# PWR_Supply-5_5V.net
KiCad netlist of a schematic drawn in Altium Designer
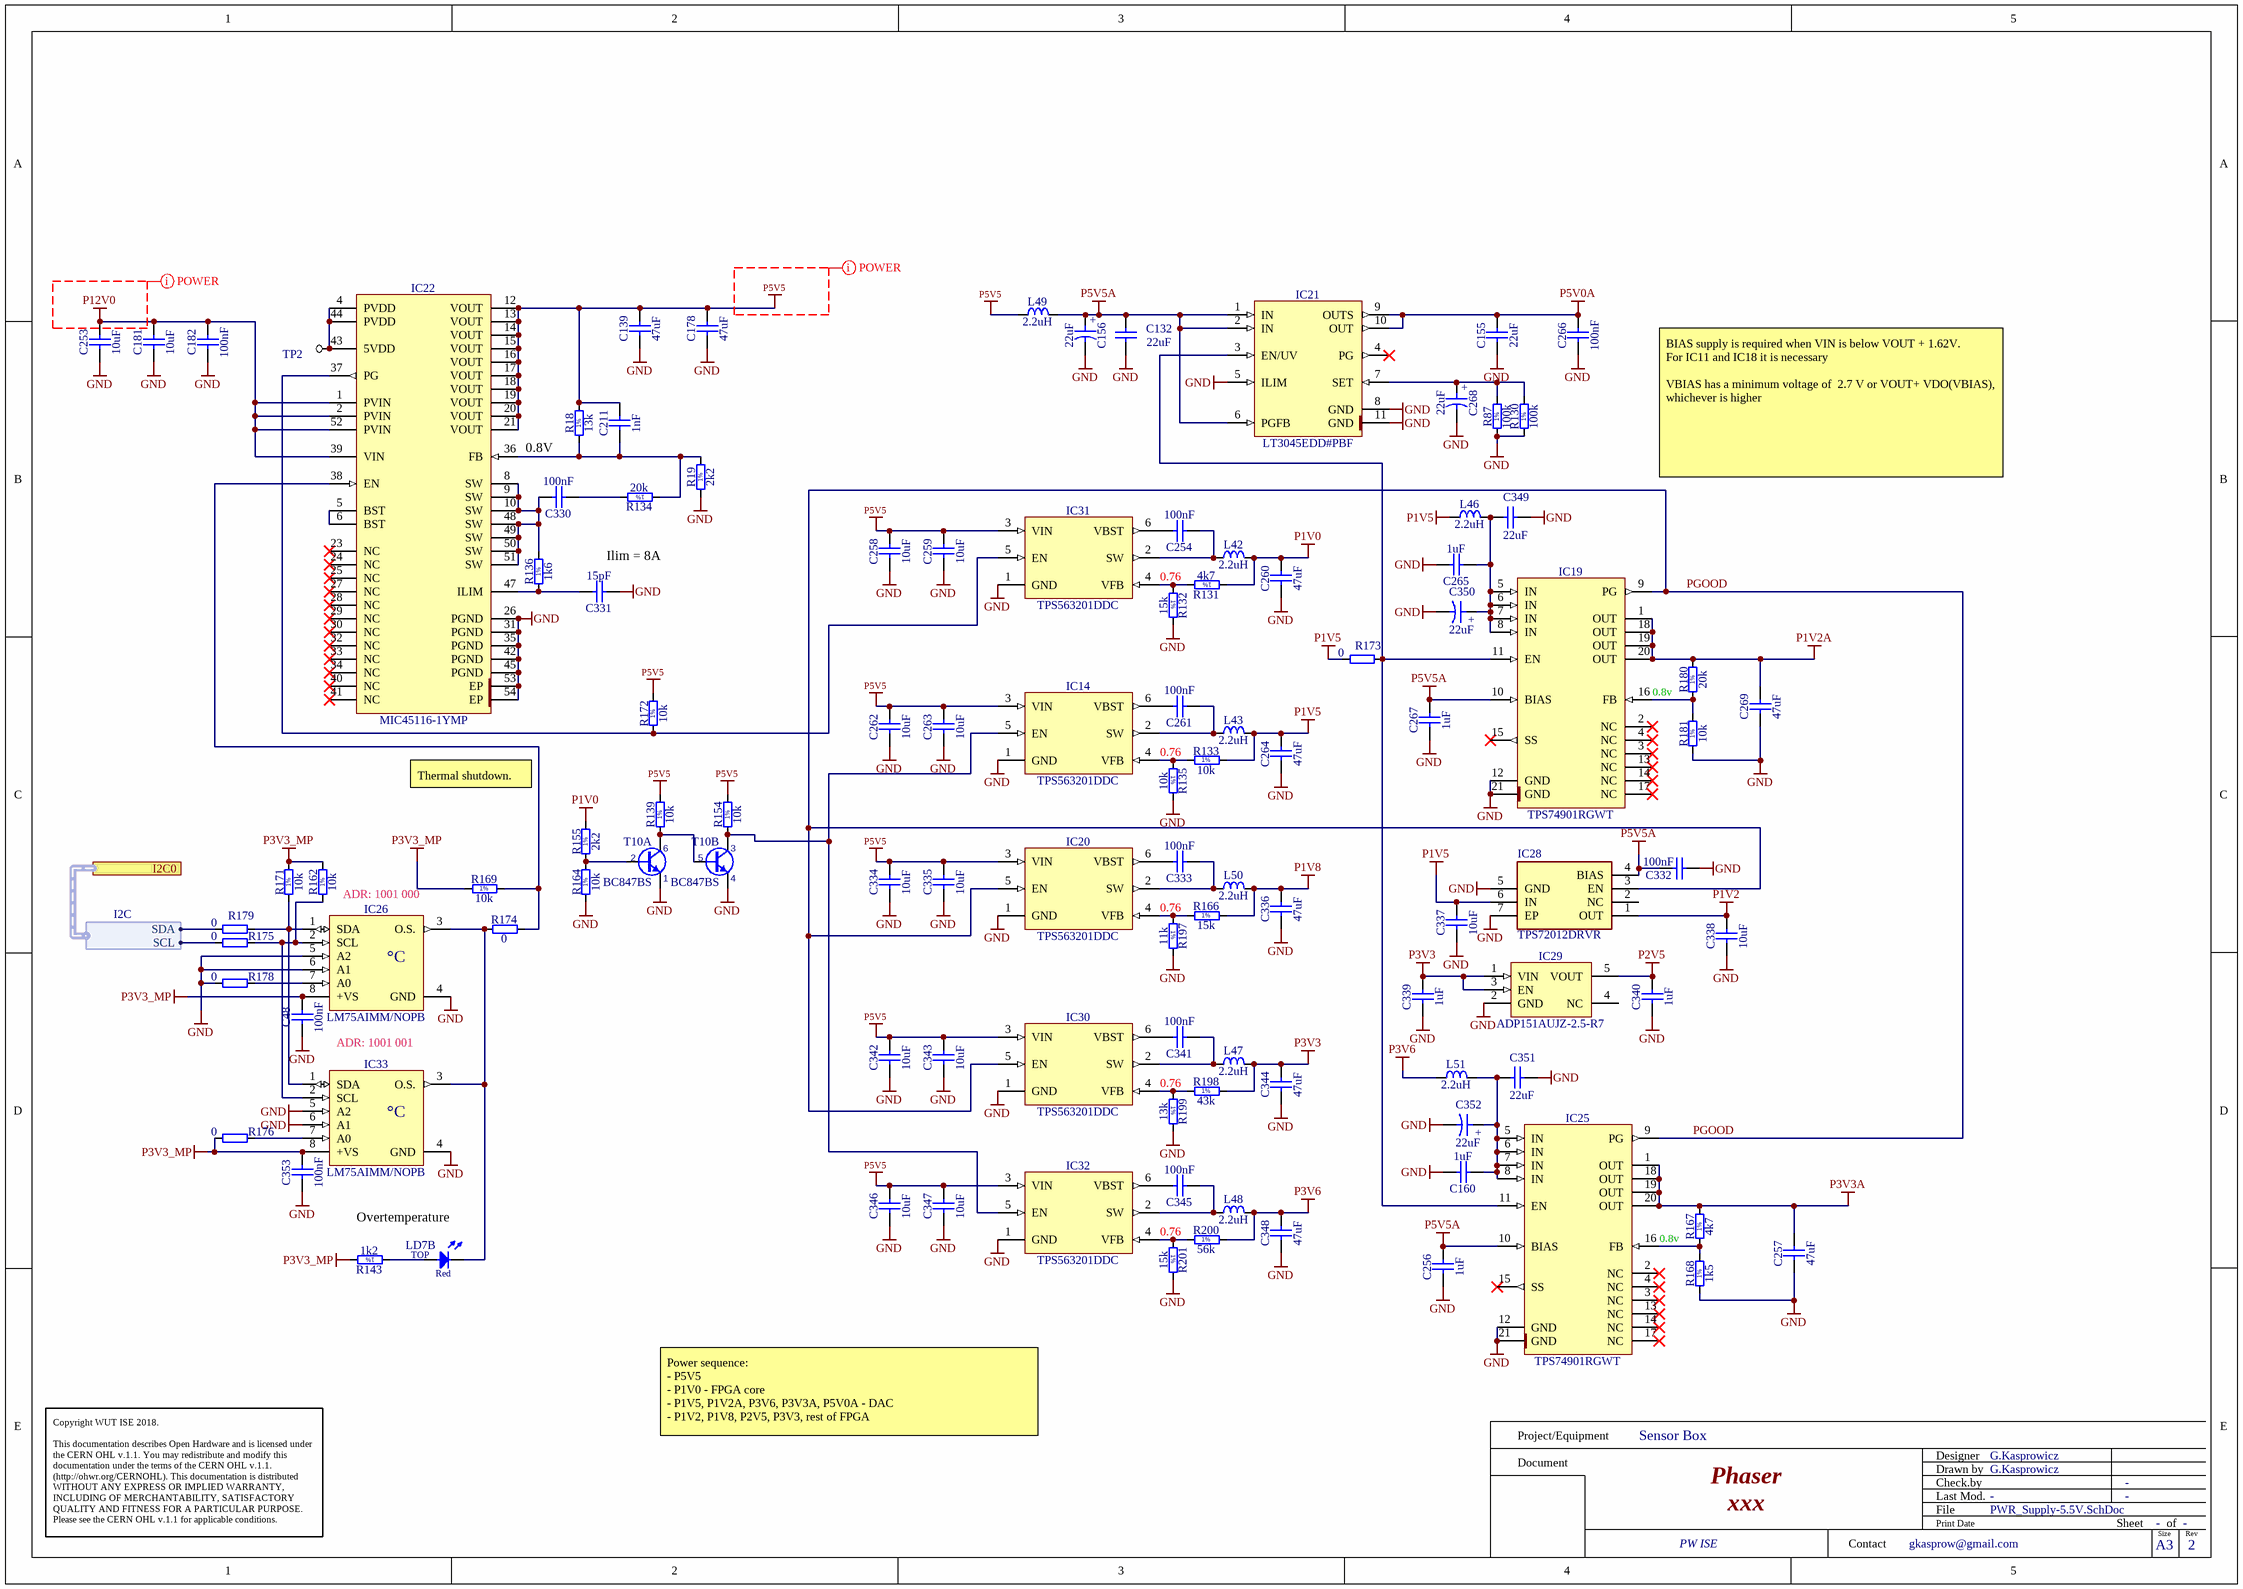
[diagram p0: PWR_Supply-5.5V.SchDoc]

(export (version "E")
  (design (tool "Eeschema 10.0.6"))
  (components
    (comp (ref "C48")
      (value "100nF")
      (footprint "CAPC1005X55N")
      (description "Non-polarised capacitor")
      (fields
        (field (name "PART NUMBER") "CC0402_100NF_16V_10%_X5R")
        (field (name "VOLTAGE") "16V")
        (field (name "AUTHOR") "CERN DEM JLC")
      )
      (libsource (lib "Capacitors") (part "Capacitor - non polarized"))
    )
    (comp (ref "C132")
      (value "22uF")
      (footprint "CAPC2012X135N")
      (description "Non-polarised capacitor")
      (fields
        (field (name "PART NUMBER") "CC0805_22UF_16V_10%_X5R")
        (field (name "VOLTAGE") "16V")
        (field (name "AUTHOR") "CERN DEM JLC")
      )
      (libsource (lib "Capacitors") (part "Capacitor - non polarized"))
    )
    (comp (ref "C139")
      (value "47uF")
      (footprint "CAPC3225X270N")
      (description "Non-polarised capacitor")
      (fields
        (field (name "PART NUMBER") "CC1210_47UF_10V_20%_X5R")
        (field (name "VOLTAGE") "10V")
        (field (name "AUTHOR") "CERN DEM JLC")
      )
      (libsource (lib "Capacitors") (part "Capacitor - non polarized"))
    )
    (comp (ref "C155")
      (value "22uF")
      (footprint "CAPC2012X135N")
      (description "Non-polarised capacitor")
      (fields
        (field (name "PART NUMBER") "CC0805_22UF_16V_10%_X5R")
        (field (name "VOLTAGE") "16V")
        (field (name "AUTHOR") "CERN DEM JLC")
      )
      (libsource (lib "Capacitors") (part "Capacitor - non polarized"))
    )
    (comp (ref "C156")
      (value "22uF")
      (footprint "CAPMP3528X210N")
      (description "Polarised capacitor")
      (fields
        (field (name "PART NUMBER") "CTE3528-21_22UF_10V_10%_LESR0700")
        (field (name "VOLTAGE") "10V")
        (field (name "AUTHOR") "CERN DEM JLC")
      )
      (libsource (lib "Capacitors") (part "Capacitor - polarized"))
    )
    (comp (ref "C160")
      (value "1uF")
      (footprint "CAPC1005X55N")
      (description "Non-polarised capacitor")
      (fields
        (field (name "PART NUMBER") "CC0402_1UF_16V_10%_X5R")
        (field (name "VOLTAGE") "16V")
        (field (name "AUTHOR") "CERN DEM JLC")
      )
      (libsource (lib "Capacitors") (part "Capacitor - non polarized"))
    )
    (comp (ref "C178")
      (value "47uF")
      (footprint "CAPC3225X270N")
      (description "Non-polarised capacitor")
      (fields
        (field (name "PART NUMBER") "CC1210_47UF_10V_20%_X5R")
        (field (name "VOLTAGE") "10V")
        (field (name "AUTHOR") "CERN DEM JLC")
      )
      (libsource (lib "Capacitors") (part "Capacitor - non polarized"))
    )
    (comp (ref "C181")
      (value "10uF")
      (footprint "CAPC2012X135N")
      (description "Non-polarised capacitor")
      (fields
        (field (name "PART NUMBER") "CC0805_10UF_16V_10%_X5R")
        (field (name "VOLTAGE") "16V")
        (field (name "AUTHOR") "CERN DEM JLC")
      )
      (libsource (lib "Capacitors") (part "Capacitor - non polarized"))
    )
    (comp (ref "C182")
      (value "100nF")
      (footprint "CAPC1005X55N")
      (description "Non-polarised capacitor")
      (fields
        (field (name "PART NUMBER") "CC0402_100NF_16V_10%_X5R")
        (field (name "VOLTAGE") "16V")
        (field (name "AUTHOR") "CERN DEM JLC")
      )
      (libsource (lib "Capacitors") (part "Capacitor - non polarized"))
    )
    (comp (ref "C211")
      (value "1nF")
      (footprint "CAPC1608X87N")
      (description "Non-polarised capacitor")
      (fields
        (field (name "PART NUMBER") "CC0603_1NF_100V_10%_X7R")
        (field (name "VOLTAGE") "100V")
        (field (name "AUTHOR") "CERN DEM JLC")
      )
      (libsource (lib "Capacitors") (part "Capacitor - non polarized"))
    )
    (comp (ref "C253")
      (value "10uF")
      (footprint "CAPC2012X135N")
      (description "Non-polarised capacitor")
      (fields
        (field (name "PART NUMBER") "CC0805_10UF_16V_10%_X5R")
        (field (name "VOLTAGE") "16V")
        (field (name "AUTHOR") "CERN DEM JLC")
      )
      (libsource (lib "Capacitors") (part "Capacitor - non polarized"))
    )
    (comp (ref "C254")
      (value "100nF")
      (footprint "CAPC1005X55N")
      (description "Non-polarised capacitor")
      (fields
        (field (name "PART NUMBER") "CC0402_100NF_16V_10%_X5R")
        (field (name "VOLTAGE") "16V")
        (field (name "AUTHOR") "CERN DEM JLC")
      )
      (libsource (lib "Capacitors") (part "Capacitor - non polarized"))
    )
    (comp (ref "C256")
      (value "1uF")
      (footprint "CAPC1005X55N")
      (description "Non-polarised capacitor")
      (fields
        (field (name "PART NUMBER") "CC0402_1UF_16V_10%_X5R")
        (field (name "VOLTAGE") "16V")
        (field (name "AUTHOR") "CERN DEM JLC")
      )
      (libsource (lib "Capacitors") (part "Capacitor - non polarized"))
    )
    (comp (ref "C257")
      (value "47uF")
      (footprint "CAPC3225X270N")
      (description "Non-polarised capacitor")
      (fields
        (field (name "PART NUMBER") "CC1210_47UF_10V_20%_X5R")
        (field (name "VOLTAGE") "10V")
        (field (name "AUTHOR") "CERN DEM JLC")
      )
      (libsource (lib "Capacitors") (part "Capacitor - non polarized"))
    )
    (comp (ref "C258")
      (value "10uF")
      (footprint "CAPC2012X135N")
      (description "Non-polarised capacitor")
      (fields
        (field (name "PART NUMBER") "CC0805_10UF_16V_10%_X5R")
        (field (name "VOLTAGE") "16V")
        (field (name "AUTHOR") "CERN DEM JLC")
      )
      (libsource (lib "Capacitors") (part "Capacitor - non polarized"))
    )
    (comp (ref "C259")
      (value "10uF")
      (footprint "CAPC2012X135N")
      (description "Non-polarised capacitor")
      (fields
        (field (name "PART NUMBER") "CC0805_10UF_16V_10%_X5R")
        (field (name "VOLTAGE") "16V")
        (field (name "AUTHOR") "CERN DEM JLC")
      )
      (libsource (lib "Capacitors") (part "Capacitor - non polarized"))
    )
    (comp (ref "C260")
      (value "47uF")
      (footprint "CAPC3225X270N")
      (description "Non-polarised capacitor")
      (fields
        (field (name "PART NUMBER") "CC1210_47UF_10V_20%_X5R")
        (field (name "VOLTAGE") "10V")
        (field (name "AUTHOR") "CERN DEM JLC")
      )
      (libsource (lib "Capacitors") (part "Capacitor - non polarized"))
    )
    (comp (ref "C261")
      (value "100nF")
      (footprint "CAPC1005X55N")
      (description "Non-polarised capacitor")
      (fields
        (field (name "PART NUMBER") "CC0402_100NF_16V_10%_X5R")
        (field (name "VOLTAGE") "16V")
        (field (name "AUTHOR") "CERN DEM JLC")
      )
      (libsource (lib "Capacitors") (part "Capacitor - non polarized"))
    )
    (comp (ref "C262")
      (value "10uF")
      (footprint "CAPC2012X135N")
      (description "Non-polarised capacitor")
      (fields
        (field (name "PART NUMBER") "CC0805_10UF_16V_10%_X5R")
        (field (name "VOLTAGE") "16V")
        (field (name "AUTHOR") "CERN DEM JLC")
      )
      (libsource (lib "Capacitors") (part "Capacitor - non polarized"))
    )
    (comp (ref "C263")
      (value "10uF")
      (footprint "CAPC2012X135N")
      (description "Non-polarised capacitor")
      (fields
        (field (name "PART NUMBER") "CC0805_10UF_16V_10%_X5R")
        (field (name "VOLTAGE") "16V")
        (field (name "AUTHOR") "CERN DEM JLC")
      )
      (libsource (lib "Capacitors") (part "Capacitor - non polarized"))
    )
    (comp (ref "C264")
      (value "47uF")
      (footprint "CAPC3225X270N")
      (description "Non-polarised capacitor")
      (fields
        (field (name "PART NUMBER") "CC1210_47UF_10V_20%_X5R")
        (field (name "VOLTAGE") "10V")
        (field (name "AUTHOR") "CERN DEM JLC")
      )
      (libsource (lib "Capacitors") (part "Capacitor - non polarized"))
    )
    (comp (ref "C265")
      (value "1uF")
      (footprint "CAPC1005X55N")
      (description "Non-polarised capacitor")
      (fields
        (field (name "PART NUMBER") "CC0402_1UF_16V_10%_X5R")
        (field (name "VOLTAGE") "16V")
        (field (name "AUTHOR") "CERN DEM JLC")
      )
      (libsource (lib "Capacitors") (part "Capacitor - non polarized"))
    )
    (comp (ref "C266")
      (value "100nF")
      (footprint "CAPC1005X55N")
      (description "Non-polarised capacitor")
      (fields
        (field (name "PART NUMBER") "CC0402_100NF_16V_10%_X5R")
        (field (name "VOLTAGE") "16V")
        (field (name "AUTHOR") "CERN DEM JLC")
      )
      (libsource (lib "Capacitors") (part "Capacitor - non polarized"))
    )
    (comp (ref "C267")
      (value "1uF")
      (footprint "CAPC1005X55N")
      (description "Non-polarised capacitor")
      (fields
        (field (name "PART NUMBER") "CC0402_1UF_16V_10%_X5R")
        (field (name "VOLTAGE") "16V")
        (field (name "AUTHOR") "CERN DEM JLC")
      )
      (libsource (lib "Capacitors") (part "Capacitor - non polarized"))
    )
    (comp (ref "C268")
      (value "22uF")
      (footprint "CAPMP3528X210N")
      (description "Polarised capacitor")
      (fields
        (field (name "PART NUMBER") "CTE3528-21_22UF_10V_10%_LESR0700")
        (field (name "VOLTAGE") "10V")
        (field (name "AUTHOR") "CERN DEM JLC")
      )
      (libsource (lib "Capacitors") (part "Capacitor - polarized"))
    )
    (comp (ref "C269")
      (value "47uF")
      (footprint "CAPC3225X270N")
      (description "Non-polarised capacitor")
      (fields
        (field (name "PART NUMBER") "CC1210_47UF_10V_20%_X5R")
        (field (name "VOLTAGE") "10V")
        (field (name "AUTHOR") "CERN DEM JLC")
      )
      (libsource (lib "Capacitors") (part "Capacitor - non polarized"))
    )
    (comp (ref "C330")
      (value "100nF")
      (footprint "CAPC1005X55N")
      (description "Non-polarised capacitor")
      (fields
        (field (name "PART NUMBER") "CC0402_100NF_16V_10%_X5R")
        (field (name "VOLTAGE") "16V")
        (field (name "AUTHOR") "CERN DEM JLC")
      )
      (libsource (lib "Capacitors") (part "Capacitor - non polarized"))
    )
    (comp (ref "C331")
      (value "15pF")
      (footprint "CAPC1005X55N")
      (description "Non-polarised capacitor")
      (fields
        (field (name "PART NUMBER") "CC0402_15PF_50V_5%_C0G")
        (field (name "VOLTAGE") "50V")
        (field (name "AUTHOR") "CERN DEM JLC")
      )
      (libsource (lib "Capacitors") (part "Capacitor - non polarized"))
    )
    (comp (ref "C332")
      (value "100nF")
      (footprint "CAPC1005X55N")
      (description "Non-polarised capacitor")
      (fields
        (field (name "PART NUMBER") "CC0402_100NF_16V_10%_X5R")
        (field (name "VOLTAGE") "16V")
        (field (name "AUTHOR") "CERN DEM JLC")
      )
      (libsource (lib "Capacitors") (part "Capacitor - non polarized"))
    )
    (comp (ref "C333")
      (value "100nF")
      (footprint "CAPC1005X55N")
      (description "Non-polarised capacitor")
      (fields
        (field (name "PART NUMBER") "CC0402_100NF_16V_10%_X5R")
        (field (name "VOLTAGE") "16V")
        (field (name "AUTHOR") "CERN DEM JLC")
      )
      (libsource (lib "Capacitors") (part "Capacitor - non polarized"))
    )
    (comp (ref "C334")
      (value "10uF")
      (footprint "CAPC2012X135N")
      (description "Non-polarised capacitor")
      (fields
        (field (name "PART NUMBER") "CC0805_10UF_16V_10%_X5R")
        (field (name "VOLTAGE") "16V")
        (field (name "AUTHOR") "CERN DEM JLC")
      )
      (libsource (lib "Capacitors") (part "Capacitor - non polarized"))
    )
    (comp (ref "C335")
      (value "10uF")
      (footprint "CAPC2012X135N")
      (description "Non-polarised capacitor")
      (fields
        (field (name "PART NUMBER") "CC0805_10UF_16V_10%_X5R")
        (field (name "VOLTAGE") "16V")
        (field (name "AUTHOR") "CERN DEM JLC")
      )
      (libsource (lib "Capacitors") (part "Capacitor - non polarized"))
    )
    (comp (ref "C336")
      (value "47uF")
      (footprint "CAPC3225X270N")
      (description "Non-polarised capacitor")
      (fields
        (field (name "PART NUMBER") "CC1210_47UF_10V_20%_X5R")
        (field (name "VOLTAGE") "10V")
        (field (name "AUTHOR") "CERN DEM JLC")
      )
      (libsource (lib "Capacitors") (part "Capacitor - non polarized"))
    )
    (comp (ref "C337")
      (value "10uF")
      (footprint "CAPC2012X135N")
      (description "Non-polarised capacitor")
      (fields
        (field (name "PART NUMBER") "CC0805_10UF_16V_10%_X5R")
        (field (name "VOLTAGE") "16V")
        (field (name "AUTHOR") "CERN DEM JLC")
      )
      (libsource (lib "Capacitors") (part "Capacitor - non polarized"))
    )
    (comp (ref "C338")
      (value "10uF")
      (footprint "CAPC2012X135N")
      (description "Non-polarised capacitor")
      (fields
        (field (name "PART NUMBER") "CC0805_10UF_16V_10%_X5R")
        (field (name "VOLTAGE") "16V")
        (field (name "AUTHOR") "CERN DEM JLC")
      )
      (libsource (lib "Capacitors") (part "Capacitor - non polarized"))
    )
    (comp (ref "C339")
      (value "1uF")
      (footprint "CAPC1608X87N")
      (description "Non-polarised capacitor")
      (fields
        (field (name "PART NUMBER") "CC0603_1UF_25V_10%_X7R")
        (field (name "VOLTAGE") "25V")
        (field (name "AUTHOR") "CERN DEM JLC")
      )
      (libsource (lib "Capacitors") (part "Capacitor - non polarized"))
    )
    (comp (ref "C340")
      (value "1uF")
      (footprint "CAPC1608X87N")
      (description "Non-polarised capacitor")
      (fields
        (field (name "PART NUMBER") "CC0603_1UF_25V_10%_X7R")
        (field (name "VOLTAGE") "25V")
        (field (name "AUTHOR") "CERN DEM JLC")
      )
      (libsource (lib "Capacitors") (part "Capacitor - non polarized"))
    )
    (comp (ref "C341")
      (value "100nF")
      (footprint "CAPC1005X55N")
      (description "Non-polarised capacitor")
      (fields
        (field (name "PART NUMBER") "CC0402_100NF_16V_10%_X5R")
        (field (name "VOLTAGE") "16V")
        (field (name "AUTHOR") "CERN DEM JLC")
      )
      (libsource (lib "Capacitors") (part "Capacitor - non polarized"))
    )
    (comp (ref "C342")
      (value "10uF")
      (footprint "CAPC2012X135N")
      (description "Non-polarised capacitor")
      (fields
        (field (name "PART NUMBER") "CC0805_10UF_16V_10%_X5R")
        (field (name "VOLTAGE") "16V")
        (field (name "AUTHOR") "CERN DEM JLC")
      )
      (libsource (lib "Capacitors") (part "Capacitor - non polarized"))
    )
    (comp (ref "C343")
      (value "10uF")
      (footprint "CAPC2012X135N")
      (description "Non-polarised capacitor")
      (fields
        (field (name "PART NUMBER") "CC0805_10UF_16V_10%_X5R")
        (field (name "VOLTAGE") "16V")
        (field (name "AUTHOR") "CERN DEM JLC")
      )
      (libsource (lib "Capacitors") (part "Capacitor - non polarized"))
    )
    (comp (ref "C344")
      (value "47uF")
      (footprint "CAPC3225X270N")
      (description "Non-polarised capacitor")
      (fields
        (field (name "PART NUMBER") "CC1210_47UF_10V_20%_X5R")
        (field (name "VOLTAGE") "10V")
        (field (name "AUTHOR") "CERN DEM JLC")
      )
      (libsource (lib "Capacitors") (part "Capacitor - non polarized"))
    )
    (comp (ref "C345")
      (value "100nF")
      (footprint "CAPC1005X55N")
      (description "Non-polarised capacitor")
      (fields
        (field (name "PART NUMBER") "CC0402_100NF_16V_10%_X5R")
        (field (name "VOLTAGE") "16V")
        (field (name "AUTHOR") "CERN DEM JLC")
      )
      (libsource (lib "Capacitors") (part "Capacitor - non polarized"))
    )
    (comp (ref "C346")
      (value "10uF")
      (footprint "CAPC2012X135N")
      (description "Non-polarised capacitor")
      (fields
        (field (name "PART NUMBER") "CC0805_10UF_16V_10%_X5R")
        (field (name "VOLTAGE") "16V")
        (field (name "AUTHOR") "CERN DEM JLC")
      )
      (libsource (lib "Capacitors") (part "Capacitor - non polarized"))
    )
    (comp (ref "C347")
      (value "10uF")
      (footprint "CAPC2012X135N")
      (description "Non-polarised capacitor")
      (fields
        (field (name "PART NUMBER") "CC0805_10UF_16V_10%_X5R")
        (field (name "VOLTAGE") "16V")
        (field (name "AUTHOR") "CERN DEM JLC")
      )
      (libsource (lib "Capacitors") (part "Capacitor - non polarized"))
    )
    (comp (ref "C348")
      (value "47uF")
      (footprint "CAPC3225X270N")
      (description "Non-polarised capacitor")
      (fields
        (field (name "PART NUMBER") "CC1210_47UF_10V_20%_X5R")
        (field (name "VOLTAGE") "10V")
        (field (name "AUTHOR") "CERN DEM JLC")
      )
      (libsource (lib "Capacitors") (part "Capacitor - non polarized"))
    )
    (comp (ref "C349")
      (value "22uF")
      (footprint "CAPC2012X135N")
      (description "Non-polarised capacitor")
      (fields
        (field (name "PART NUMBER") "CC0805_22UF_16V_10%_X5R")
        (field (name "VOLTAGE") "16V")
        (field (name "AUTHOR") "CERN DEM JLC")
      )
      (libsource (lib "Capacitors") (part "Capacitor - non polarized"))
    )
    (comp (ref "C350")
      (value "22uF")
      (footprint "CAPMP3528X210N")
      (description "Polarised capacitor")
      (fields
        (field (name "PART NUMBER") "CTE3528-21_22UF_10V_10%_LESR0700")
        (field (name "VOLTAGE") "10V")
        (field (name "AUTHOR") "CERN DEM JLC")
      )
      (libsource (lib "Capacitors") (part "Capacitor - polarized"))
    )
    (comp (ref "C351")
      (value "22uF")
      (footprint "CAPC2012X135N")
      (description "Non-polarised capacitor")
      (fields
        (field (name "PART NUMBER") "CC0805_22UF_16V_10%_X5R")
        (field (name "VOLTAGE") "16V")
        (field (name "AUTHOR") "CERN DEM JLC")
      )
      (libsource (lib "Capacitors") (part "Capacitor - non polarized"))
    )
    (comp (ref "C352")
      (value "22uF")
      (footprint "CAPMP3528X210N")
      (description "Polarised capacitor")
      (fields
        (field (name "PART NUMBER") "CTE3528-21_22UF_10V_10%_LESR0700")
        (field (name "VOLTAGE") "10V")
        (field (name "AUTHOR") "CERN DEM JLC")
      )
      (libsource (lib "Capacitors") (part "Capacitor - polarized"))
    )
    (comp (ref "C353")
      (value "100nF")
      (footprint "CAPC1005X55N")
      (description "Non-polarised capacitor")
      (fields
        (field (name "PART NUMBER") "CC0402_100NF_16V_10%_X5R")
        (field (name "VOLTAGE") "16V")
        (field (name "AUTHOR") "CERN DEM JLC")
      )
      (libsource (lib "Capacitors") (part "Capacitor - non polarized"))
    )
    (comp (ref "IC14")
      (value "TPS563201DDC")
      (footprint "SOT95P280X110-6N")
      (description "4.5V to 17V Input, 3A Synchronous Step-Down Voltage Regulator")
      (fields (field (name "MANUFACTURER") "TEXAS INSTRUMENTS") (field (name "AUTHOR") "CERN DEM MR"))
      (libsource (lib "ICs And Semiconductors") (part "TPS563201"))
    )
    (comp (ref "IC19")
      (value "TPS74901RGWT")
      (footprint "QFN65P500X500X100-21N-S325")
      (description "3A, 0.8 to 3.6V Adjustable Low-Dropout Linear Regulator with Programmable Soft-Start")
      (fields (field (name "MANUFACTURER") "TEXAS INSTRUMENTS") (field (name "AUTHOR") "CERN DEM JLC"))
      (libsource (lib "ICs And Semiconductors") (part "TPS74901RGWT"))
    )
    (comp (ref "IC20")
      (value "TPS563201DDC")
      (footprint "SOT95P280X110-6N")
      (description "4.5V to 17V Input, 3A Synchronous Step-Down Voltage Regulator")
      (fields (field (name "MANUFACTURER") "TEXAS INSTRUMENTS") (field (name "AUTHOR") "CERN DEM MR"))
      (libsource (lib "ICs And Semiconductors") (part "TPS563201"))
    )
    (comp (ref "IC21")
      (value "LT3045EDD#PBF")
      (footprint "SON50P300X300X80-11N-R175X248")
      (description "20V, 500mA, Ultralow Noise, Ultrahigh PSRR Linear Regulator")
      (fields (field (name "MANUFACTURER") "LINEAR TECHNOLOGY") (field (name "AUTHOR") "CERN DEM JLC"))
      (libsource (lib "ICs And Semiconductors") (part "LT3045EDD"))
    )
    (comp (ref "IC22")
      (value "MIC45116-1YMP")
      (footprint "MICROCHIP_H3QFN88-52LD-PL-3")
      (description "0.8V to 85% PVIN (4.75-19V), 6A Synchronous Step-Down Regulator Module")
      (fields (field (name "MANUFACTURER") "MICROCHIP TECHNOLOGY") (field (name "AUTHOR") "CERN DEM JMW"))
      (libsource (lib "ICs And Semiconductors") (part "MIC45116"))
    )
    (comp (ref "IC25")
      (value "TPS74901RGWT")
      (footprint "QFN65P500X500X100-21N-S325")
      (description "3A, 0.8 to 3.6V Adjustable Low-Dropout Linear Regulator with Programmable Soft-Start")
      (fields (field (name "MANUFACTURER") "TEXAS INSTRUMENTS") (field (name "AUTHOR") "CERN DEM JLC"))
      (libsource (lib "ICs And Semiconductors") (part "TPS74901RGWT"))
    )
    (comp (ref "IC26")
      (value "LM75AIMM/NOPB")
      (footprint "SOP65P490X109-8N")
      (description "Digital Temperature Sensor and Thermal Watchdog with Two-Wire Interface")
      (fields (field (name "MANUFACTURER") "TEXAS INSTRUMENTS") (field (name "AUTHOR") "CERN DEM JLC"))
      (libsource (lib "ICs And Semiconductors") (part "LM75"))
    )
    (comp (ref "IC28")
      (value "TPS72012DRVR")
      (footprint "SamacSys:SON65P200X200X80-7N")
      (description "Integrated Circuit")
      (fields (field (name "MOUSER PART NUMBER") "595-TPS72012DRVR"))
      (libsource (lib "*") (part "TPS72012DRVR"))
    )
    (comp (ref "IC29")
      (value "ADP151AUJZ-2.5-R7")
      (footprint "SOT95P280X90-5N")
      (description "Ultralow Noise, 200 mA CMOS Linear Regulator")
      (fields (field (name "MANUFACTURER") "ANALOG DEVICES") (field (name "AUTHOR") "CERN DEM JLC"))
      (libsource (lib "ICs And Semiconductors") (part "ADP151AUJZ"))
    )
    (comp (ref "IC30")
      (value "TPS563201DDC")
      (footprint "SOT95P280X110-6N")
      (description "4.5V to 17V Input, 3A Synchronous Step-Down Voltage Regulator")
      (fields (field (name "MANUFACTURER") "TEXAS INSTRUMENTS") (field (name "AUTHOR") "CERN DEM MR"))
      (libsource (lib "ICs And Semiconductors") (part "TPS563201"))
    )
    (comp (ref "IC31")
      (value "TPS563201DDC")
      (footprint "SOT95P280X110-6N")
      (description "4.5V to 17V Input, 3A Synchronous Step-Down Voltage Regulator")
      (fields (field (name "MANUFACTURER") "TEXAS INSTRUMENTS") (field (name "AUTHOR") "CERN DEM MR"))
      (libsource (lib "ICs And Semiconductors") (part "TPS563201"))
    )
    (comp (ref "IC32")
      (value "TPS563201DDC")
      (footprint "SOT95P280X110-6N")
      (description "4.5V to 17V Input, 3A Synchronous Step-Down Voltage Regulator")
      (fields (field (name "MANUFACTURER") "TEXAS INSTRUMENTS") (field (name "AUTHOR") "CERN DEM MR"))
      (libsource (lib "ICs And Semiconductors") (part "TPS563201"))
    )
    (comp (ref "IC33")
      (value "LM75AIMM/NOPB")
      (footprint "SOP65P490X109-8N")
      (description "Digital Temperature Sensor and Thermal Watchdog with Two-Wire Interface")
      (fields (field (name "MANUFACTURER") "TEXAS INSTRUMENTS") (field (name "AUTHOR") "CERN DEM JLC"))
      (libsource (lib "ICs And Semiconductors") (part "LM75"))
    )
    (comp (ref "L42")
      (value "2.2uH")
      (footprint "IND_BOURNS_SRP5015TA")
      (description "Inductor")
      (fields
        (field (name "PART NUMBER") "IND_2.2UH_20%_BOURNS_SRP5015TA")
        (field (name "POWER") "4A")
        (field (name "AUTHOR") "CERN DEM JMW")
      )
      (libsource (lib "Inductors & Transformers") (part "Inductor"))
    )
    (comp (ref "L43")
      (value "2.2uH")
      (footprint "IND_BOURNS_SRP5015TA")
      (description "Inductor")
      (fields
        (field (name "PART NUMBER") "IND_2.2UH_20%_BOURNS_SRP5015TA")
        (field (name "POWER") "4A")
        (field (name "AUTHOR") "CERN DEM JMW")
      )
      (libsource (lib "Inductors & Transformers") (part "Inductor"))
    )
    (comp (ref "L46")
      (value "2.2uH")
      (footprint "IND_BOURNS_SRP5015TA")
      (description "Inductor")
      (fields
        (field (name "PART NUMBER") "IND_2.2UH_20%_BOURNS_SRP5015TA")
        (field (name "POWER") "4A")
        (field (name "AUTHOR") "CERN DEM JMW")
      )
      (libsource (lib "Inductors & Transformers") (part "Inductor"))
    )
    (comp (ref "L47")
      (value "2.2uH")
      (footprint "IND_BOURNS_SRP5015TA")
      (description "Inductor")
      (fields
        (field (name "PART NUMBER") "IND_2.2UH_20%_BOURNS_SRP5015TA")
        (field (name "POWER") "4A")
        (field (name "AUTHOR") "CERN DEM JMW")
      )
      (libsource (lib "Inductors & Transformers") (part "Inductor"))
    )
    (comp (ref "L48")
      (value "2.2uH")
      (footprint "IND_BOURNS_SRP5015TA")
      (description "Inductor")
      (fields
        (field (name "PART NUMBER") "IND_2.2UH_20%_BOURNS_SRP5015TA")
        (field (name "POWER") "4A")
        (field (name "AUTHOR") "CERN DEM JMW")
      )
      (libsource (lib "Inductors & Transformers") (part "Inductor"))
    )
    (comp (ref "L49")
      (value "2.2uH")
      (footprint "IND_BOURNS_SRP5015TA")
      (description "Inductor")
      (fields
        (field (name "PART NUMBER") "IND_2.2UH_20%_BOURNS_SRP5015TA")
        (field (name "POWER") "4A")
        (field (name "AUTHOR") "CERN DEM JMW")
      )
      (libsource (lib "Inductors & Transformers") (part "Inductor"))
    )
    (comp (ref "L50")
      (value "2.2uH")
      (footprint "IND_BOURNS_SRP5015TA")
      (description "Inductor")
      (fields
        (field (name "PART NUMBER") "IND_2.2UH_20%_BOURNS_SRP5015TA")
        (field (name "POWER") "4A")
        (field (name "AUTHOR") "CERN DEM JMW")
      )
      (libsource (lib "Inductors & Transformers") (part "Inductor"))
    )
    (comp (ref "L51")
      (value "2.2uH")
      (footprint "IND_BOURNS_SRP5015TA")
      (description "Inductor")
      (fields
        (field (name "PART NUMBER") "IND_2.2UH_20%_BOURNS_SRP5015TA")
        (field (name "POWER") "4A")
        (field (name "AUTHOR") "CERN DEM JMW")
      )
      (libsource (lib "Inductors & Transformers") (part "Inductor"))
    )
    (comp (ref "LD7")
      (value "Red/Green")
      (footprint "LED_DIALIGHT_571-0112F")
      (description "2x LED  Botom Green, Top Red")
      (fields
        (field (name "PART NUMBER") "LED_DIALIGHT_571-0112F")
        (field (name "MANUFACTURER") "DIALIGHT")
        (field (name "AUTHOR") "CERN DEM JLC")
      )
      (libsource (lib "ICs And Semiconductors") (part "LED x2 G-1C2A-BOT_R-3C4A-TOP"))
    )
    (comp (ref "R18")
      (value "13k")
      (footprint "RESC1005X40N")
      (description "Resistor - 1%")
      (fields
        (field (name "PART NUMBER") "R0402_13K_1%_0.0625W_100PPM")
        (field (name "POWER") "0.0625W")
        (field (name "AUTHOR") "CERN DEM JLC")
      )
      (libsource (lib "Resistors") (part "Resistor - 1%"))
    )
    (comp (ref "R19")
      (value "2k2")
      (footprint "RESC1608X55N")
      (description "Resistor - 1%")
      (fields
        (field (name "PART NUMBER") "R0603_2K2_1%_0.1W_100PPM")
        (field (name "POWER") "0.1W")
        (field (name "AUTHOR") "CERN DEM JLC")
      )
      (libsource (lib "Resistors") (part "Resistor - 1%"))
    )
    (comp (ref "R87")
      (value "100k")
      (footprint "RESC1005X40N")
      (description "Resistor - 1%")
      (fields
        (field (name "PART NUMBER") "R0402_100K_1%_0.0625W_100PPM")
        (field (name "POWER") "0.0625W")
        (field (name "AUTHOR") "CERN DEM JLC")
      )
      (libsource (lib "Resistors") (part "Resistor - 1%"))
    )
    (comp (ref "R130")
      (value "100k")
      (footprint "RESC1005X40N")
      (description "Resistor - 1%")
      (fields
        (field (name "PART NUMBER") "R0402_100K_1%_0.0625W_100PPM")
        (field (name "POWER") "0.0625W")
        (field (name "AUTHOR") "CERN DEM JLC")
      )
      (libsource (lib "Resistors") (part "Resistor - 1%"))
    )
    (comp (ref "R131")
      (value "4k7")
      (footprint "RESC1005X40N")
      (description "Resistor - 1%")
      (fields
        (field (name "PART NUMBER") "R0402_4K7_1%_0.0625W_100PPM")
        (field (name "POWER") "0.0625W")
        (field (name "AUTHOR") "CERN DEM JLC")
      )
      (libsource (lib "Resistors") (part "Resistor - 1%"))
    )
    (comp (ref "R132")
      (value "15k")
      (footprint "RESC1005X40N")
      (description "Resistor - 1%")
      (fields
        (field (name "PART NUMBER") "R0402_15K_1%_0.0625W_100PPM")
        (field (name "POWER") "0.0625W")
        (field (name "AUTHOR") "CERN DEM JMW")
      )
      (libsource (lib "Resistors") (part "Resistor - 1%"))
    )
    (comp (ref "R133")
      (value "10k")
      (footprint "RESC1005X40N")
      (description "Resistor - 1%")
      (fields
        (field (name "PART NUMBER") "R0402_10K_1%_0.0625W_100PPM")
        (field (name "POWER") "0.0625W")
        (field (name "AUTHOR") "CERN DEM JLC")
      )
      (libsource (lib "Resistors") (part "Resistor - 1%"))
    )
    (comp (ref "R134")
      (value "20k")
      (footprint "RESC1005X40N")
      (description "Resistor - 1%")
      (fields
        (field (name "PART NUMBER") "R0402_20K_1%_0.0625W_100PPM")
        (field (name "POWER") "0.0625W")
        (field (name "AUTHOR") "CERN DEM JLC")
      )
      (libsource (lib "Resistors") (part "Resistor - 1%"))
    )
    (comp (ref "R135")
      (value "10k")
      (footprint "RESC1005X40N")
      (description "Resistor - 1%")
      (fields
        (field (name "PART NUMBER") "R0402_10K_1%_0.0625W_100PPM")
        (field (name "POWER") "0.0625W")
        (field (name "AUTHOR") "CERN DEM JLC")
      )
      (libsource (lib "Resistors") (part "Resistor - 1%"))
    )
    (comp (ref "R136")
      (value "1k6")
      (footprint "RESC1005X40N")
      (description "Resistor - 1%")
      (fields
        (field (name "PART NUMBER") "R0402_1K6_1%_0.0625W_100PPM")
        (field (name "POWER") "0.0625W")
        (field (name "AUTHOR") "CERN DEM JLC")
      )
      (libsource (lib "Resistors") (part "Resistor - 1%"))
    )
    (comp (ref "R139")
      (value "10k")
      (footprint "RESC1005X40N")
      (description "Resistor - 1%")
      (fields
        (field (name "PART NUMBER") "R0402_10K_1%_0.0625W_100PPM")
        (field (name "POWER") "0.0625W")
        (field (name "AUTHOR") "CERN DEM JLC")
      )
      (libsource (lib "Resistors") (part "Resistor - 1%"))
    )
    (comp (ref "R143")
      (value "1k2")
      (footprint "RESC1608X55N")
      (description "Resistor - 1%")
      (fields
        (field (name "PART NUMBER") "R0603_1K2_1%_0.1W_100PPM")
        (field (name "POWER") "0.1W")
        (field (name "AUTHOR") "CERN DEM JLC")
      )
      (libsource (lib "Resistors") (part "Resistor - 1%"))
    )
    (comp (ref "R154")
      (value "10k")
      (footprint "RESC1005X40N")
      (description "Resistor - 1%")
      (fields
        (field (name "PART NUMBER") "R0402_10K_1%_0.0625W_100PPM")
        (field (name "POWER") "0.0625W")
        (field (name "AUTHOR") "CERN DEM JLC")
      )
      (libsource (lib "Resistors") (part "Resistor - 1%"))
    )
    (comp (ref "R155")
      (value "2k2")
      (footprint "RESC1608X55N")
      (description "Resistor - 1%")
      (fields
        (field (name "PART NUMBER") "R0603_2K2_1%_0.1W_100PPM")
        (field (name "POWER") "0.1W")
        (field (name "AUTHOR") "CERN DEM JLC")
      )
      (libsource (lib "Resistors") (part "Resistor - 1%"))
    )
    (comp (ref "R162")
      (value "10k")
      (footprint "RESC1005X40N")
      (description "Resistor - 1%")
      (fields
        (field (name "PART NUMBER") "R0402_10K_1%_0.0625W_100PPM")
        (field (name "POWER") "0.0625W")
        (field (name "AUTHOR") "CERN DEM JLC")
      )
      (libsource (lib "Resistors") (part "Resistor - 1%"))
    )
    (comp (ref "R164")
      (value "10k")
      (footprint "RESC1005X40N")
      (description "Resistor - 1%")
      (fields
        (field (name "PART NUMBER") "R0402_10K_1%_0.0625W_100PPM")
        (field (name "POWER") "0.0625W")
        (field (name "AUTHOR") "CERN DEM JLC")
      )
      (libsource (lib "Resistors") (part "Resistor - 1%"))
    )
    (comp (ref "R166")
      (value "15k")
      (footprint "RESC1005X40N")
      (description "Resistor - 1%")
      (fields
        (field (name "PART NUMBER") "R0402_15K_1%_0.0625W_100PPM")
        (field (name "POWER") "0.0625W")
        (field (name "AUTHOR") "CERN DEM JMW")
      )
      (libsource (lib "Resistors") (part "Resistor - 1%"))
    )
    (comp (ref "R167")
      (value "4k7")
      (footprint "RESC1608X55N")
      (description "Resistor - 1%")
      (fields
        (field (name "PART NUMBER") "R0603_4K7_1%_0.1W_100PPM")
        (field (name "POWER") "0.1W")
        (field (name "AUTHOR") "CERN DEM JLC")
      )
      (libsource (lib "Resistors") (part "Resistor - 1%"))
    )
    (comp (ref "R168")
      (value "1k5")
      (footprint "RESC1608X55N")
      (description "Resistor - 1%")
      (fields
        (field (name "PART NUMBER") "R0603_1K5_1%_0.1W_100PPM")
        (field (name "POWER") "0.1W")
        (field (name "AUTHOR") "CERN DEM JLC")
      )
      (libsource (lib "Resistors") (part "Resistor - 1%"))
    )
    (comp (ref "R169")
      (value "10k")
      (footprint "RESC1005X40N")
      (description "Resistor - 1%")
      (fields
        (field (name "PART NUMBER") "R0402_10K_1%_0.0625W_100PPM")
        (field (name "POWER") "0.0625W")
        (field (name "AUTHOR") "CERN DEM JLC")
      )
      (libsource (lib "Resistors") (part "Resistor - 1%"))
    )
    (comp (ref "R171")
      (value "10k")
      (footprint "RESC1005X40N")
      (description "Resistor - 1%")
      (fields
        (field (name "PART NUMBER") "R0402_10K_1%_0.0625W_100PPM")
        (field (name "POWER") "0.0625W")
        (field (name "AUTHOR") "CERN DEM JLC")
      )
      (libsource (lib "Resistors") (part "Resistor - 1%"))
    )
    (comp (ref "R172")
      (value "10k")
      (footprint "RESC1005X40N")
      (description "Resistor - 1%")
      (fields
        (field (name "PART NUMBER") "R0402_10K_1%_0.0625W_100PPM")
        (field (name "POWER") "0.0625W")
        (field (name "AUTHOR") "CERN DEM JLC")
      )
      (libsource (lib "Resistors") (part "Resistor - 1%"))
    )
    (comp (ref "R173")
      (value "0")
      (footprint "RESC1005X40N")
      (description "Resistor")
      (fields
        (field (name "PART NUMBER") "R0402_0R_JUMPER")
        (field (name "MANUFACTURER") "GENERIC")
        (field (name "AUTHOR") "CERN DEM JLC")
      )
      (libsource (lib "Resistors") (part "Resistor"))
    )
    (comp (ref "R174")
      (value "0")
      (footprint "RESC1005X40N")
      (description "Resistor")
      (fields
        (field (name "PART NUMBER") "R0402_0R_JUMPER")
        (field (name "MANUFACTURER") "GENERIC")
        (field (name "AUTHOR") "CERN DEM JLC")
      )
      (libsource (lib "Resistors") (part "Resistor"))
    )
    (comp (ref "R175")
      (value "0")
      (footprint "RESC1005X40N")
      (description "Resistor")
      (fields
        (field (name "PART NUMBER") "R0402_0R_JUMPER")
        (field (name "MANUFACTURER") "GENERIC")
        (field (name "AUTHOR") "CERN DEM JLC")
      )
      (libsource (lib "Resistors") (part "Resistor"))
    )
    (comp (ref "R176")
      (value "0")
      (footprint "RESC1005X40N")
      (description "Resistor")
      (fields
        (field (name "PART NUMBER") "R0402_0R_JUMPER")
        (field (name "MANUFACTURER") "GENERIC")
        (field (name "AUTHOR") "CERN DEM JLC")
      )
      (libsource (lib "Resistors") (part "Resistor"))
    )
    (comp (ref "R178")
      (value "0")
      (footprint "RESC1005X40N")
      (description "Resistor")
      (fields
        (field (name "PART NUMBER") "R0402_0R_JUMPER")
        (field (name "MANUFACTURER") "GENERIC")
        (field (name "AUTHOR") "CERN DEM JLC")
      )
      (libsource (lib "Resistors") (part "Resistor"))
    )
    (comp (ref "R179")
      (value "0")
      (footprint "RESC1005X40N")
      (description "Resistor")
      (fields
        (field (name "PART NUMBER") "R0402_0R_JUMPER")
        (field (name "MANUFACTURER") "GENERIC")
        (field (name "AUTHOR") "CERN DEM JLC")
      )
      (libsource (lib "Resistors") (part "Resistor"))
    )
    (comp (ref "R180")
      (value "20k")
      (footprint "RESC1608X55N")
      (description "Resistor - 1%")
      (fields
        (field (name "PART NUMBER") "R0603_20K_1%_0.1W_100PPM")
        (field (name "POWER") "0.1W")
        (field (name "AUTHOR") "CERN DEM JLC")
      )
      (libsource (lib "Resistors") (part "Resistor - 1%"))
    )
    (comp (ref "R181")
      (value "10k")
      (footprint "RESC1608X55N")
      (description "Resistor - 1%")
      (fields
        (field (name "PART NUMBER") "R0603_10K_1%_0.1W_100PPM")
        (field (name "POWER") "0.1W")
        (field (name "AUTHOR") "CERN DEM JLC")
      )
      (libsource (lib "Resistors") (part "Resistor - 1%"))
    )
    (comp (ref "R197")
      (value "11k")
      (footprint "RESC1005X40N")
      (description "Resistor - 1%")
      (fields
        (field (name "PART NUMBER") "R0402_11K_1%_0.0625W_100PPM")
        (field (name "POWER") "0.0625W")
        (field (name "AUTHOR") "CERN DEM JLC")
      )
      (libsource (lib "Resistors") (part "Resistor - 1%"))
    )
    (comp (ref "R198")
      (value "43k")
      (footprint "RESC1005X40N")
      (description "Resistor - 1%")
      (fields
        (field (name "PART NUMBER") "R0402_43K_1%_0.0625W_100PPM")
        (field (name "POWER") "0.0625W")
        (field (name "AUTHOR") "CERN DEM JLC")
      )
      (libsource (lib "Resistors") (part "Resistor - 1%"))
    )
    (comp (ref "R199")
      (value "13k")
      (footprint "RESC1005X40N")
      (description "Resistor - 1%")
      (fields
        (field (name "PART NUMBER") "R0402_13K_1%_0.0625W_100PPM")
        (field (name "POWER") "0.0625W")
        (field (name "AUTHOR") "CERN DEM JLC")
      )
      (libsource (lib "Resistors") (part "Resistor - 1%"))
    )
    (comp (ref "R200")
      (value "56k")
      (footprint "RESC1005X40N")
      (description "Resistor - 1%")
      (fields
        (field (name "PART NUMBER") "R0402_56K_1%_0.0625W_100PPM")
        (field (name "POWER") "0.0625W")
        (field (name "AUTHOR") "CERN DEM JLC")
      )
      (libsource (lib "Resistors") (part "Resistor - 1%"))
    )
    (comp (ref "R201")
      (value "15k")
      (footprint "RESC1005X40N")
      (description "Resistor - 1%")
      (fields
        (field (name "PART NUMBER") "R0402_15K_1%_0.0625W_100PPM")
        (field (name "POWER") "0.0625W")
        (field (name "AUTHOR") "CERN DEM JMW")
      )
      (libsource (lib "Resistors") (part "Resistor - 1%"))
    )
    (comp (ref "T10")
      (value "BC847BS")
      (footprint "SOT65P210X110-6N")
      (description "45V 100mA Dual NPN General-Purpose Transistor")
      (fields (field (name "MANUFACTURER") "NXP SEMICONDUCTORS") (field (name "AUTHOR") "CERN DEM JMW"))
      (libsource (lib "ICs And Semiconductors") (part "BC847BS"))
    )
    (comp (ref "TP2")
      (value "TP")
      (footprint "TP")
      (description "Testpoint")
      (libsource (lib "LIBRARY_SCH") (part "TP"))
    )
  )
  (nets
    (net (code "2") (name "/PGOOD") (class "Default")
      (node (ref "IC19") (pin "9") (pinfunction "PG_9") (pintype "output"))
      (node (ref "IC20") (pin "5") (pinfunction "EN_5") (pintype "input"))
      (node (ref "IC25") (pin "9") (pinfunction "PG_9") (pintype "output"))
      (node (ref "IC28") (pin "3") (pinfunction "EN_3") (pintype "passive"))
      (node (ref "IC30") (pin "5") (pinfunction "EN_5") (pintype "input"))
    )
    (net (code "3") (name "/SCL") (class "Default")
      (node (ref "R175") (pin "1") (pinfunction "1_1") (pintype "passive"))
    )
    (net (code "4") (name "/SDA") (class "Default")
      (node (ref "R179") (pin "1") (pinfunction "1_1") (pintype "passive"))
    )
    (net (code "6") (name "GND") (class "Default")
      (node (ref "C132") (pin "1") (pinfunction "1_1") (pintype "passive"))
      (node (ref "C139") (pin "1") (pinfunction "1_1") (pintype "passive"))
      (node (ref "C155") (pin "1") (pinfunction "1_1") (pintype "passive"))
      (node (ref "C156") (pin "2") (pinfunction "2_2") (pintype "passive"))
      (node (ref "C160") (pin "2") (pinfunction "2_2") (pintype "passive"))
      (node (ref "C178") (pin "1") (pinfunction "1_1") (pintype "passive"))
      (node (ref "C181") (pin "1") (pinfunction "1_1") (pintype "passive"))
      (node (ref "C182") (pin "1") (pinfunction "1_1") (pintype "passive"))
      (node (ref "C253") (pin "1") (pinfunction "1_1") (pintype "passive"))
      (node (ref "C256") (pin "1") (pinfunction "1_1") (pintype "passive"))
      (node (ref "C257") (pin "1") (pinfunction "1_1") (pintype "passive"))
      (node (ref "C258") (pin "1") (pinfunction "1_1") (pintype "passive"))
      (node (ref "C259") (pin "1") (pinfunction "1_1") (pintype "passive"))
      (node (ref "C260") (pin "1") (pinfunction "1_1") (pintype "passive"))
      (node (ref "C262") (pin "1") (pinfunction "1_1") (pintype "passive"))
      (node (ref "C263") (pin "1") (pinfunction "1_1") (pintype "passive"))
      (node (ref "C264") (pin "1") (pinfunction "1_1") (pintype "passive"))
      (node (ref "C265") (pin "2") (pinfunction "2_2") (pintype "passive"))
      (node (ref "C266") (pin "1") (pinfunction "1_1") (pintype "passive"))
      (node (ref "C267") (pin "1") (pinfunction "1_1") (pintype "passive"))
      (node (ref "C268") (pin "2") (pinfunction "2_2") (pintype "passive"))
      (node (ref "C269") (pin "1") (pinfunction "1_1") (pintype "passive"))
      (node (ref "C331") (pin "1") (pinfunction "1_1") (pintype "passive"))
      (node (ref "C332") (pin "1") (pinfunction "1_1") (pintype "passive"))
      (node (ref "C334") (pin "1") (pinfunction "1_1") (pintype "passive"))
      (node (ref "C335") (pin "1") (pinfunction "1_1") (pintype "passive"))
      (node (ref "C336") (pin "1") (pinfunction "1_1") (pintype "passive"))
      (node (ref "C337") (pin "1") (pinfunction "1_1") (pintype "passive"))
      (node (ref "C338") (pin "1") (pinfunction "1_1") (pintype "passive"))
      (node (ref "C339") (pin "1") (pinfunction "1_1") (pintype "passive"))
      (node (ref "C340") (pin "1") (pinfunction "1_1") (pintype "passive"))
      (node (ref "C342") (pin "1") (pinfunction "1_1") (pintype "passive"))
      (node (ref "C343") (pin "1") (pinfunction "1_1") (pintype "passive"))
      (node (ref "C344") (pin "1") (pinfunction "1_1") (pintype "passive"))
      (node (ref "C346") (pin "1") (pinfunction "1_1") (pintype "passive"))
      (node (ref "C347") (pin "1") (pinfunction "1_1") (pintype "passive"))
      (node (ref "C348") (pin "1") (pinfunction "1_1") (pintype "passive"))
      (node (ref "C349") (pin "1") (pinfunction "1_1") (pintype "passive"))
      (node (ref "C350") (pin "2") (pinfunction "2_2") (pintype "passive"))
      (node (ref "C351") (pin "1") (pinfunction "1_1") (pintype "passive"))
      (node (ref "C352") (pin "2") (pinfunction "2_2") (pintype "passive"))
      (node (ref "C353") (pin "1") (pinfunction "1_1") (pintype "passive"))
      (node (ref "C48") (pin "1") (pinfunction "1_1") (pintype "passive"))
      (node (ref "IC14") (pin "1") (pinfunction "GND_1") (pintype "power_in"))
      (node (ref "IC19") (pin "12") (pinfunction "GND_12") (pintype "power_in"))
      (node (ref "IC19") (pin "21") (pinfunction "GND_21") (pintype "power_in"))
      (node (ref "IC20") (pin "1") (pinfunction "GND_1") (pintype "power_in"))
      (node (ref "IC21") (pin "11") (pinfunction "GND_11") (pintype "power_in"))
      (node (ref "IC21") (pin "5") (pinfunction "ILIM_5") (pintype "input"))
      (node (ref "IC21") (pin "8") (pinfunction "GND_8") (pintype "power_in"))
      (node (ref "IC22") (pin "26") (pinfunction "PGND_26") (pintype "power_in"))
      (node (ref "IC22") (pin "31") (pinfunction "PGND_31") (pintype "power_in"))
      (node (ref "IC22") (pin "35") (pinfunction "PGND_35") (pintype "power_in"))
      (node (ref "IC22") (pin "42") (pinfunction "PGND_42") (pintype "power_in"))
      (node (ref "IC22") (pin "45") (pinfunction "PGND_45") (pintype "power_in"))
      (node (ref "IC22") (pin "53") (pinfunction "EP_53") (pintype "power_in"))
      (node (ref "IC22") (pin "54") (pinfunction "EP_54") (pintype "power_in"))
      (node (ref "IC25") (pin "12") (pinfunction "GND_12") (pintype "power_in"))
      (node (ref "IC25") (pin "21") (pinfunction "GND_21") (pintype "power_in"))
      (node (ref "IC26") (pin "4") (pinfunction "GND_4") (pintype "power_in"))
      (node (ref "IC26") (pin "5") (pinfunction "A2_5") (pintype "input"))
      (node (ref "IC26") (pin "6") (pinfunction "A1_6") (pintype "input"))
      (node (ref "IC28") (pin "5") (pinfunction "GND_5") (pintype "passive"))
      (node (ref "IC28") (pin "7") (pinfunction "EP_7") (pintype "passive"))
      (node (ref "IC29") (pin "2") (pinfunction "GND_2") (pintype "power_in"))
      (node (ref "IC30") (pin "1") (pinfunction "GND_1") (pintype "power_in"))
      (node (ref "IC31") (pin "1") (pinfunction "GND_1") (pintype "power_in"))
      (node (ref "IC32") (pin "1") (pinfunction "GND_1") (pintype "power_in"))
      (node (ref "IC33") (pin "4") (pinfunction "GND_4") (pintype "power_in"))
      (node (ref "IC33") (pin "5") (pinfunction "A2_5") (pintype "input"))
      (node (ref "IC33") (pin "6") (pinfunction "A1_6") (pintype "input"))
      (node (ref "R130") (pin "1") (pinfunction "1_1") (pintype "passive"))
      (node (ref "R132") (pin "2") (pinfunction "2_2") (pintype "passive"))
      (node (ref "R135") (pin "2") (pinfunction "2_2") (pintype "passive"))
      (node (ref "R164") (pin "1") (pinfunction "1_1") (pintype "passive"))
      (node (ref "R168") (pin "1") (pinfunction "1_1") (pintype "passive"))
      (node (ref "R178") (pin "1") (pinfunction "1_1") (pintype "passive"))
      (node (ref "R181") (pin "1") (pinfunction "1_1") (pintype "passive"))
      (node (ref "R19") (pin "1") (pinfunction "1_1") (pintype "passive"))
      (node (ref "R197") (pin "2") (pinfunction "2_2") (pintype "passive"))
      (node (ref "R199") (pin "2") (pinfunction "2_2") (pintype "passive"))
      (node (ref "R201") (pin "2") (pinfunction "2_2") (pintype "passive"))
      (node (ref "R87") (pin "1") (pinfunction "1_1") (pintype "passive"))
      (node (ref "T10") (pin "1") (pinfunction "E_1") (pintype "passive"))
      (node (ref "T10") (pin "4") (pinfunction "E_4") (pintype "passive"))
    )
    (net (code "7") (name "Net-(C160-Pad1)") (class "Default")
      (node (ref "C160") (pin "1") (pinfunction "1_1") (pintype "passive"))
      (node (ref "C351") (pin "2") (pinfunction "2_2") (pintype "passive"))
      (node (ref "C352") (pin "1") (pinfunction "1_1") (pintype "passive"))
      (node (ref "IC25") (pin "5") (pinfunction "IN_5") (pintype "input"))
      (node (ref "IC25") (pin "6") (pinfunction "IN_6") (pintype "input"))
      (node (ref "IC25") (pin "7") (pinfunction "IN_7") (pintype "input"))
      (node (ref "IC25") (pin "8") (pinfunction "IN_8") (pintype "input"))
      (node (ref "L51") (pin "2") (pinfunction "2_2") (pintype "passive"))
    )
    (net (code "8") (name "Net-(C265-Pad1)") (class "Default")
      (node (ref "C265") (pin "1") (pinfunction "1_1") (pintype "passive"))
      (node (ref "C349") (pin "2") (pinfunction "2_2") (pintype "passive"))
      (node (ref "C350") (pin "1") (pinfunction "1_1") (pintype "passive"))
      (node (ref "IC19") (pin "5") (pinfunction "IN_5") (pintype "input"))
      (node (ref "IC19") (pin "6") (pinfunction "IN_6") (pintype "input"))
      (node (ref "IC19") (pin "7") (pinfunction "IN_7") (pintype "input"))
      (node (ref "IC19") (pin "8") (pinfunction "IN_8") (pintype "input"))
      (node (ref "L46") (pin "2") (pinfunction "2_2") (pintype "passive"))
    )
    (net (code "9") (name "Net-(C330-Pad1)") (class "Default")
      (node (ref "C330") (pin "1") (pinfunction "1_1") (pintype "passive"))
      (node (ref "R134") (pin "2") (pinfunction "2_2") (pintype "passive"))
    )
    (net (code "10") (name "Net-(C330-Pad2)") (class "Default")
      (node (ref "C330") (pin "2") (pinfunction "2_2") (pintype "passive"))
      (node (ref "IC22") (pin "10") (pinfunction "SW_10") (pintype "passive"))
      (node (ref "IC22") (pin "48") (pinfunction "SW_48") (pintype "passive"))
      (node (ref "IC22") (pin "49") (pinfunction "SW_49") (pintype "passive"))
      (node (ref "IC22") (pin "50") (pinfunction "SW_50") (pintype "passive"))
      (node (ref "IC22") (pin "51") (pinfunction "SW_51") (pintype "passive"))
      (node (ref "IC22") (pin "8") (pinfunction "SW_8") (pintype "passive"))
      (node (ref "IC22") (pin "9") (pinfunction "SW_9") (pintype "passive"))
      (node (ref "R136") (pin "2") (pinfunction "2_2") (pintype "passive"))
    )
    (net (code "11") (name "Net-(IC14-EN)") (class "Default")
      (node (ref "IC14") (pin "5") (pinfunction "EN_5") (pintype "input"))
      (node (ref "IC32") (pin "5") (pinfunction "EN_5") (pintype "input"))
      (node (ref "R154") (pin "1") (pinfunction "1_1") (pintype "passive"))
      (node (ref "T10") (pin "3") (pinfunction "C_3") (pintype "passive"))
    )
    (net (code "12") (name "Net-(IC14-SW)") (class "Default")
      (node (ref "C261") (pin "1") (pinfunction "1_1") (pintype "passive"))
      (node (ref "IC14") (pin "2") (pinfunction "SW_2") (pintype "output"))
      (node (ref "L43") (pin "1") (pinfunction "1_1") (pintype "passive"))
    )
    (net (code "13") (name "Net-(IC14-VBST)") (class "Default")
      (node (ref "C261") (pin "2") (pinfunction "2_2") (pintype "passive"))
      (node (ref "IC14") (pin "6") (pinfunction "VBST_6") (pintype "output"))
    )
    (net (code "14") (name "Net-(IC14-VFB)") (class "Default")
      (node (ref "IC14") (pin "4") (pinfunction "VFB_4") (pintype "input"))
      (node (ref "R133") (pin "1") (pinfunction "1_1") (pintype "passive"))
      (node (ref "R135") (pin "1") (pinfunction "1_1") (pintype "passive"))
    )
    (net (code "15") (name "Net-(IC19-EN)") (class "Default")
      (node (ref "IC19") (pin "11") (pinfunction "EN_11") (pintype "input"))
      (node (ref "IC21") (pin "3") (pinfunction "EN/UV_3") (pintype "input"))
      (node (ref "IC25") (pin "11") (pinfunction "EN_11") (pintype "input"))
      (node (ref "R173") (pin "2") (pinfunction "2_2") (pintype "passive"))
    )
    (net (code "16") (name "Net-(IC19-FB)") (class "Default")
      (node (ref "IC19") (pin "16") (pinfunction "FB_16") (pintype "input"))
      (node (ref "R180") (pin "1") (pinfunction "1_1") (pintype "passive"))
      (node (ref "R181") (pin "2") (pinfunction "2_2") (pintype "passive"))
    )
    (net (code "17") (name "Net-(IC20-SW)") (class "Default")
      (node (ref "C333") (pin "1") (pinfunction "1_1") (pintype "passive"))
      (node (ref "IC20") (pin "2") (pinfunction "SW_2") (pintype "output"))
      (node (ref "L50") (pin "1") (pinfunction "1_1") (pintype "passive"))
    )
    (net (code "18") (name "Net-(IC20-VBST)") (class "Default")
      (node (ref "C333") (pin "2") (pinfunction "2_2") (pintype "passive"))
      (node (ref "IC20") (pin "6") (pinfunction "VBST_6") (pintype "output"))
    )
    (net (code "19") (name "Net-(IC20-VFB)") (class "Default")
      (node (ref "IC20") (pin "4") (pinfunction "VFB_4") (pintype "input"))
      (node (ref "R166") (pin "1") (pinfunction "1_1") (pintype "passive"))
      (node (ref "R197") (pin "1") (pinfunction "1_1") (pintype "passive"))
    )
    (net (code "20") (name "Net-(IC21-SET)") (class "Default")
      (node (ref "C268") (pin "1") (pinfunction "1_1") (pintype "passive"))
      (node (ref "IC21") (pin "7") (pinfunction "SET_7") (pintype "input"))
      (node (ref "R130") (pin "2") (pinfunction "2_2") (pintype "passive"))
      (node (ref "R87") (pin "2") (pinfunction "2_2") (pintype "passive"))
    )
    (net (code "21") (name "Net-(IC22-5VDD)") (class "Default")
      (node (ref "IC22") (pin "4") (pinfunction "PVDD_4") (pintype "power_in"))
      (node (ref "IC22") (pin "43") (pinfunction "5VDD_43") (pintype "power_in"))
      (node (ref "IC22") (pin "44") (pinfunction "PVDD_44") (pintype "power_in"))
      (node (ref "TP2") (pin "1") (pintype "passive"))
    )
    (net (code "22") (name "Net-(IC22-BST-Pad5)") (class "Default")
      (node (ref "IC22") (pin "5") (pinfunction "BST_5") (pintype "passive"))
      (node (ref "IC22") (pin "6") (pinfunction "BST_6") (pintype "passive"))
    )
    (net (code "23") (name "Net-(IC22-EN)") (class "Default")
      (node (ref "IC22") (pin "38") (pinfunction "EN_38") (pintype "input"))
      (node (ref "R169") (pin "2") (pinfunction "2_2") (pintype "passive"))
      (node (ref "R174") (pin "2") (pinfunction "2_2") (pintype "passive"))
    )
    (net (code "24") (name "Net-(IC22-FB)") (class "Default")
      (node (ref "C211") (pin "1") (pinfunction "1_1") (pintype "passive"))
      (node (ref "IC22") (pin "36") (pinfunction "FB_36") (pintype "input"))
      (node (ref "R134") (pin "1") (pinfunction "1_1") (pintype "passive"))
      (node (ref "R18") (pin "1") (pinfunction "1_1") (pintype "passive"))
      (node (ref "R19") (pin "2") (pinfunction "2_2") (pintype "passive"))
    )
    (net (code "25") (name "Net-(IC22-ILIM)") (class "Default")
      (node (ref "C331") (pin "2") (pinfunction "2_2") (pintype "passive"))
      (node (ref "IC22") (pin "47") (pinfunction "ILIM_47") (pintype "passive"))
      (node (ref "R136") (pin "1") (pinfunction "1_1") (pintype "passive"))
    )
    (net (code "26") (name "Net-(IC22-PG)") (class "Default")
      (node (ref "IC22") (pin "37") (pinfunction "PG_37") (pintype "output"))
      (node (ref "IC31") (pin "5") (pinfunction "EN_5") (pintype "input"))
      (node (ref "R172") (pin "1") (pinfunction "1_1") (pintype "passive"))
    )
    (net (code "27") (name "Net-(IC25-FB)") (class "Default")
      (node (ref "IC25") (pin "16") (pinfunction "FB_16") (pintype "input"))
      (node (ref "R167") (pin "1") (pinfunction "1_1") (pintype "passive"))
      (node (ref "R168") (pin "2") (pinfunction "2_2") (pintype "passive"))
    )
    (net (code "28") (name "Net-(IC26-A0)") (class "Default")
      (node (ref "IC26") (pin "7") (pinfunction "A0_7") (pintype "input"))
      (node (ref "R178") (pin "2") (pinfunction "2_2") (pintype "passive"))
    )
    (net (code "29") (name "Net-(IC26-O.S.)") (class "Default")
      (node (ref "IC26") (pin "3") (pinfunction "O.S._3") (pintype "output"))
      (node (ref "IC33") (pin "3") (pinfunction "O.S._3") (pintype "output"))
      (node (ref "LD7") (pin "3") (pinfunction "C_3") (pintype "passive"))
      (node (ref "R174") (pin "1") (pinfunction "1_1") (pintype "passive"))
    )
    (net (code "30") (name "Net-(IC26-SCL)") (class "Default")
      (node (ref "IC26") (pin "2") (pinfunction "SCL_2") (pintype "input"))
      (node (ref "IC33") (pin "2") (pinfunction "SCL_2") (pintype "input"))
      (node (ref "R162") (pin "1") (pinfunction "1_1") (pintype "passive"))
      (node (ref "R175") (pin "2") (pinfunction "2_2") (pintype "passive"))
    )
    (net (code "31") (name "Net-(IC26-SDA)") (class "Default")
      (node (ref "IC26") (pin "1") (pinfunction "SDA_1") (pintype "bidirectional"))
      (node (ref "IC33") (pin "1") (pinfunction "SDA_1") (pintype "bidirectional"))
      (node (ref "R171") (pin "1") (pinfunction "1_1") (pintype "passive"))
      (node (ref "R179") (pin "2") (pinfunction "2_2") (pintype "passive"))
    )
    (net (code "32") (name "Net-(IC30-SW)") (class "Default")
      (node (ref "C341") (pin "1") (pinfunction "1_1") (pintype "passive"))
      (node (ref "IC30") (pin "2") (pinfunction "SW_2") (pintype "output"))
      (node (ref "L47") (pin "1") (pinfunction "1_1") (pintype "passive"))
    )
    (net (code "33") (name "Net-(IC30-VBST)") (class "Default")
      (node (ref "C341") (pin "2") (pinfunction "2_2") (pintype "passive"))
      (node (ref "IC30") (pin "6") (pinfunction "VBST_6") (pintype "output"))
    )
    (net (code "34") (name "Net-(IC30-VFB)") (class "Default")
      (node (ref "IC30") (pin "4") (pinfunction "VFB_4") (pintype "input"))
      (node (ref "R198") (pin "1") (pinfunction "1_1") (pintype "passive"))
      (node (ref "R199") (pin "1") (pinfunction "1_1") (pintype "passive"))
    )
    (net (code "35") (name "Net-(IC31-SW)") (class "Default")
      (node (ref "C254") (pin "1") (pinfunction "1_1") (pintype "passive"))
      (node (ref "IC31") (pin "2") (pinfunction "SW_2") (pintype "output"))
      (node (ref "L42") (pin "1") (pinfunction "1_1") (pintype "passive"))
    )
    (net (code "36") (name "Net-(IC31-VBST)") (class "Default")
      (node (ref "C254") (pin "2") (pinfunction "2_2") (pintype "passive"))
      (node (ref "IC31") (pin "6") (pinfunction "VBST_6") (pintype "output"))
    )
    (net (code "37") (name "Net-(IC31-VFB)") (class "Default")
      (node (ref "IC31") (pin "4") (pinfunction "VFB_4") (pintype "input"))
      (node (ref "R131") (pin "2") (pinfunction "2_2") (pintype "passive"))
      (node (ref "R132") (pin "1") (pinfunction "1_1") (pintype "passive"))
    )
    (net (code "38") (name "Net-(IC32-SW)") (class "Default")
      (node (ref "C345") (pin "1") (pinfunction "1_1") (pintype "passive"))
      (node (ref "IC32") (pin "2") (pinfunction "SW_2") (pintype "output"))
      (node (ref "L48") (pin "1") (pinfunction "1_1") (pintype "passive"))
    )
    (net (code "39") (name "Net-(IC32-VBST)") (class "Default")
      (node (ref "C345") (pin "2") (pinfunction "2_2") (pintype "passive"))
      (node (ref "IC32") (pin "6") (pinfunction "VBST_6") (pintype "output"))
    )
    (net (code "40") (name "Net-(IC32-VFB)") (class "Default")
      (node (ref "IC32") (pin "4") (pinfunction "VFB_4") (pintype "input"))
      (node (ref "R200") (pin "1") (pinfunction "1_1") (pintype "passive"))
      (node (ref "R201") (pin "1") (pinfunction "1_1") (pintype "passive"))
    )
    (net (code "41") (name "Net-(IC33-A0)") (class "Default")
      (node (ref "IC33") (pin "7") (pinfunction "A0_7") (pintype "input"))
      (node (ref "R176") (pin "2") (pinfunction "2_2") (pintype "passive"))
    )
    (net (code "42") (name "Net-(LD7B-A)") (class "Default")
      (node (ref "LD7") (pin "4") (pinfunction "A_4") (pintype "passive"))
      (node (ref "R143") (pin "1") (pinfunction "1_1") (pintype "passive"))
    )
    (net (code "43") (name "Net-(T10A-B)") (class "Default")
      (node (ref "R155") (pin "1") (pinfunction "1_1") (pintype "passive"))
      (node (ref "R164") (pin "2") (pinfunction "2_2") (pintype "passive"))
      (node (ref "T10") (pin "2") (pinfunction "B_2") (pintype "passive"))
    )
    (net (code "44") (name "Net-(T10A-C)") (class "Default")
      (node (ref "R139") (pin "1") (pinfunction "1_1") (pintype "passive"))
      (node (ref "T10") (pin "5") (pinfunction "B_5") (pintype "passive"))
      (node (ref "T10") (pin "6") (pinfunction "C_6") (pintype "passive"))
    )
    (net (code "45") (name "P1V0") (class "Default")
      (node (ref "C260") (pin "2") (pinfunction "2_2") (pintype "passive"))
      (node (ref "L42") (pin "2") (pinfunction "2_2") (pintype "passive"))
      (node (ref "R131") (pin "1") (pinfunction "1_1") (pintype "passive"))
      (node (ref "R155") (pin "2") (pinfunction "2_2") (pintype "passive"))
    )
    (net (code "46") (name "P1V2") (class "Default")
      (node (ref "C338") (pin "2") (pinfunction "2_2") (pintype "passive"))
      (node (ref "IC28") (pin "1") (pinfunction "OUT_1") (pintype "passive"))
    )
    (net (code "47") (name "P1V2A") (class "Default")
      (node (ref "C269") (pin "2") (pinfunction "2_2") (pintype "passive"))
      (node (ref "IC19") (pin "1") (pinfunction "OUT_1") (pintype "power_in"))
      (node (ref "IC19") (pin "18") (pinfunction "OUT_18") (pintype "power_in"))
      (node (ref "IC19") (pin "19") (pinfunction "OUT_19") (pintype "power_in"))
      (node (ref "IC19") (pin "20") (pinfunction "OUT_20") (pintype "power_in"))
      (node (ref "R180") (pin "2") (pinfunction "2_2") (pintype "passive"))
    )
    (net (code "48") (name "P1V5") (class "Default")
      (node (ref "C264") (pin "2") (pinfunction "2_2") (pintype "passive"))
      (node (ref "C337") (pin "2") (pinfunction "2_2") (pintype "passive"))
      (node (ref "IC28") (pin "6") (pinfunction "IN_6") (pintype "passive"))
      (node (ref "L43") (pin "2") (pinfunction "2_2") (pintype "passive"))
      (node (ref "L46") (pin "1") (pinfunction "1_1") (pintype "passive"))
      (node (ref "R133") (pin "2") (pinfunction "2_2") (pintype "passive"))
      (node (ref "R173") (pin "1") (pinfunction "1_1") (pintype "passive"))
    )
    (net (code "49") (name "P1V8") (class "Default")
      (node (ref "C336") (pin "2") (pinfunction "2_2") (pintype "passive"))
      (node (ref "L50") (pin "2") (pinfunction "2_2") (pintype "passive"))
      (node (ref "R166") (pin "2") (pinfunction "2_2") (pintype "passive"))
    )
    (net (code "50") (name "P2V5") (class "Default")
      (node (ref "C340") (pin "2") (pinfunction "2_2") (pintype "passive"))
      (node (ref "IC29") (pin "5") (pinfunction "VOUT_5") (pintype "power_in"))
    )
    (net (code "51") (name "P3V3") (class "Default")
      (node (ref "C339") (pin "2") (pinfunction "2_2") (pintype "passive"))
      (node (ref "C344") (pin "2") (pinfunction "2_2") (pintype "passive"))
      (node (ref "IC29") (pin "1") (pinfunction "VIN_1") (pintype "input"))
      (node (ref "IC29") (pin "3") (pinfunction "EN_3") (pintype "input"))
      (node (ref "L47") (pin "2") (pinfunction "2_2") (pintype "passive"))
      (node (ref "R198") (pin "2") (pinfunction "2_2") (pintype "passive"))
    )
    (net (code "52") (name "P3V3A") (class "Default")
      (node (ref "C257") (pin "2") (pinfunction "2_2") (pintype "passive"))
      (node (ref "IC25") (pin "1") (pinfunction "OUT_1") (pintype "power_in"))
      (node (ref "IC25") (pin "18") (pinfunction "OUT_18") (pintype "power_in"))
      (node (ref "IC25") (pin "19") (pinfunction "OUT_19") (pintype "power_in"))
      (node (ref "IC25") (pin "20") (pinfunction "OUT_20") (pintype "power_in"))
      (node (ref "R167") (pin "2") (pinfunction "2_2") (pintype "passive"))
    )
    (net (code "53") (name "P3V3_MP") (class "Default")
      (node (ref "C353") (pin "2") (pinfunction "2_2") (pintype "passive"))
      (node (ref "C48") (pin "2") (pinfunction "2_2") (pintype "passive"))
      (node (ref "IC26") (pin "8") (pinfunction "+VS_8") (pintype "power_in"))
      (node (ref "IC33") (pin "8") (pinfunction "+VS_8") (pintype "power_in"))
      (node (ref "R143") (pin "2") (pinfunction "2_2") (pintype "passive"))
      (node (ref "R162") (pin "2") (pinfunction "2_2") (pintype "passive"))
      (node (ref "R169") (pin "1") (pinfunction "1_1") (pintype "passive"))
      (node (ref "R171") (pin "2") (pinfunction "2_2") (pintype "passive"))
      (node (ref "R176") (pin "1") (pinfunction "1_1") (pintype "passive"))
    )
    (net (code "54") (name "P3V6") (class "Default")
      (node (ref "C348") (pin "2") (pinfunction "2_2") (pintype "passive"))
      (node (ref "L48") (pin "2") (pinfunction "2_2") (pintype "passive"))
      (node (ref "L51") (pin "1") (pinfunction "1_1") (pintype "passive"))
      (node (ref "R200") (pin "2") (pinfunction "2_2") (pintype "passive"))
    )
    (net (code "55") (name "P5V0A") (class "Default")
      (node (ref "C155") (pin "2") (pinfunction "2_2") (pintype "passive"))
      (node (ref "C266") (pin "2") (pinfunction "2_2") (pintype "passive"))
      (node (ref "IC21") (pin "10") (pinfunction "OUT_10") (pintype "output"))
      (node (ref "IC21") (pin "9") (pinfunction "OUTS_9") (pintype "output"))
    )
    (net (code "56") (name "P5V5") (class "Default")
      (node (ref "C139") (pin "2") (pinfunction "2_2") (pintype "passive"))
      (node (ref "C178") (pin "2") (pinfunction "2_2") (pintype "passive"))
      (node (ref "C211") (pin "2") (pinfunction "2_2") (pintype "passive"))
      (node (ref "C258") (pin "2") (pinfunction "2_2") (pintype "passive"))
      (node (ref "C259") (pin "2") (pinfunction "2_2") (pintype "passive"))
      (node (ref "C262") (pin "2") (pinfunction "2_2") (pintype "passive"))
      (node (ref "C263") (pin "2") (pinfunction "2_2") (pintype "passive"))
      (node (ref "C334") (pin "2") (pinfunction "2_2") (pintype "passive"))
      (node (ref "C335") (pin "2") (pinfunction "2_2") (pintype "passive"))
      (node (ref "C342") (pin "2") (pinfunction "2_2") (pintype "passive"))
      (node (ref "C343") (pin "2") (pinfunction "2_2") (pintype "passive"))
      (node (ref "C346") (pin "2") (pinfunction "2_2") (pintype "passive"))
      (node (ref "C347") (pin "2") (pinfunction "2_2") (pintype "passive"))
      (node (ref "IC14") (pin "3") (pinfunction "VIN_3") (pintype "input"))
      (node (ref "IC20") (pin "3") (pinfunction "VIN_3") (pintype "input"))
      (node (ref "IC22") (pin "12") (pinfunction "VOUT_12") (pintype "power_in"))
      (node (ref "IC22") (pin "13") (pinfunction "VOUT_13") (pintype "power_in"))
      (node (ref "IC22") (pin "14") (pinfunction "VOUT_14") (pintype "power_in"))
      (node (ref "IC22") (pin "15") (pinfunction "VOUT_15") (pintype "power_in"))
      (node (ref "IC22") (pin "16") (pinfunction "VOUT_16") (pintype "power_in"))
      (node (ref "IC22") (pin "17") (pinfunction "VOUT_17") (pintype "power_in"))
      (node (ref "IC22") (pin "18") (pinfunction "VOUT_18") (pintype "power_in"))
      (node (ref "IC22") (pin "19") (pinfunction "VOUT_19") (pintype "power_in"))
      (node (ref "IC22") (pin "20") (pinfunction "VOUT_20") (pintype "power_in"))
      (node (ref "IC22") (pin "21") (pinfunction "VOUT_21") (pintype "power_in"))
      (node (ref "IC30") (pin "3") (pinfunction "VIN_3") (pintype "input"))
      (node (ref "IC31") (pin "3") (pinfunction "VIN_3") (pintype "input"))
      (node (ref "IC32") (pin "3") (pinfunction "VIN_3") (pintype "input"))
      (node (ref "L49") (pin "1") (pinfunction "1_1") (pintype "passive"))
      (node (ref "R139") (pin "2") (pinfunction "2_2") (pintype "passive"))
      (node (ref "R154") (pin "2") (pinfunction "2_2") (pintype "passive"))
      (node (ref "R172") (pin "2") (pinfunction "2_2") (pintype "passive"))
      (node (ref "R18") (pin "2") (pinfunction "2_2") (pintype "passive"))
    )
    (net (code "57") (name "P5V5A") (class "Default")
      (node (ref "C132") (pin "2") (pinfunction "2_2") (pintype "passive"))
      (node (ref "C156") (pin "1") (pinfunction "1_1") (pintype "passive"))
      (node (ref "C256") (pin "2") (pinfunction "2_2") (pintype "passive"))
      (node (ref "C267") (pin "2") (pinfunction "2_2") (pintype "passive"))
      (node (ref "C332") (pin "2") (pinfunction "2_2") (pintype "passive"))
      (node (ref "IC19") (pin "10") (pinfunction "BIAS_10") (pintype "input"))
      (node (ref "IC21") (pin "1") (pinfunction "IN_1") (pintype "input"))
      (node (ref "IC21") (pin "2") (pinfunction "IN_2") (pintype "input"))
      (node (ref "IC21") (pin "6") (pinfunction "PGFB_6") (pintype "input"))
      (node (ref "IC25") (pin "10") (pinfunction "BIAS_10") (pintype "input"))
      (node (ref "IC28") (pin "4") (pinfunction "BIAS_4") (pintype "passive"))
      (node (ref "L49") (pin "2") (pinfunction "2_2") (pintype "passive"))
    )
    (net (code "58") (name "P12V0") (class "Default")
      (node (ref "C181") (pin "2") (pinfunction "2_2") (pintype "passive"))
      (node (ref "C182") (pin "2") (pinfunction "2_2") (pintype "passive"))
      (node (ref "C253") (pin "2") (pinfunction "2_2") (pintype "passive"))
      (node (ref "IC22") (pin "1") (pinfunction "PVIN_1") (pintype "power_in"))
      (node (ref "IC22") (pin "2") (pinfunction "PVIN_2") (pintype "power_in"))
      (node (ref "IC22") (pin "39") (pinfunction "VIN_39") (pintype "power_in"))
      (node (ref "IC22") (pin "52") (pinfunction "PVIN_52") (pintype "power_in"))
    )
    (net (code "59") (name "unconnected-(IC19-NC-Pad2)") (class "Default")
      (node (ref "IC19") (pin "2") (pinfunction "NC_2") (pintype "passive+no_connect"))
    )
    (net (code "60") (name "unconnected-(IC19-NC-Pad3)") (class "Default")
      (node (ref "IC19") (pin "3") (pinfunction "NC_3") (pintype "passive+no_connect"))
    )
    (net (code "61") (name "unconnected-(IC19-NC-Pad4)") (class "Default")
      (node (ref "IC19") (pin "4") (pinfunction "NC_4") (pintype "passive+no_connect"))
    )
    (net (code "62") (name "unconnected-(IC19-NC-Pad13)") (class "Default")
      (node (ref "IC19") (pin "13") (pinfunction "NC_13") (pintype "passive+no_connect"))
    )
    (net (code "63") (name "unconnected-(IC19-NC-Pad14)") (class "Default")
      (node (ref "IC19") (pin "14") (pinfunction "NC_14") (pintype "passive+no_connect"))
    )
    (net (code "64") (name "unconnected-(IC19-NC-Pad17)") (class "Default")
      (node (ref "IC19") (pin "17") (pinfunction "NC_17") (pintype "passive+no_connect"))
    )
    (net (code "65") (name "unconnected-(IC19-SS-Pad15)") (class "Default")
      (node (ref "IC19") (pin "15") (pinfunction "SS_15") (pintype "output+no_connect"))
    )
    (net (code "66") (name "unconnected-(IC21-PG-Pad4)") (class "Default")
      (node (ref "IC21") (pin "4") (pinfunction "PG_4") (pintype "output+no_connect"))
    )
    (net (code "67") (name "unconnected-(IC22-NC-Pad23)") (class "Default")
      (node (ref "IC22") (pin "23") (pinfunction "NC_23") (pintype "passive+no_connect"))
    )
    (net (code "68") (name "unconnected-(IC22-NC-Pad24)") (class "Default")
      (node (ref "IC22") (pin "24") (pinfunction "NC_24") (pintype "passive+no_connect"))
    )
    (net (code "69") (name "unconnected-(IC22-NC-Pad25)") (class "Default")
      (node (ref "IC22") (pin "25") (pinfunction "NC_25") (pintype "passive+no_connect"))
    )
    (net (code "70") (name "unconnected-(IC22-NC-Pad27)") (class "Default")
      (node (ref "IC22") (pin "27") (pinfunction "NC_27") (pintype "passive+no_connect"))
    )
    (net (code "71") (name "unconnected-(IC22-NC-Pad28)") (class "Default")
      (node (ref "IC22") (pin "28") (pinfunction "NC_28") (pintype "passive+no_connect"))
    )
    (net (code "72") (name "unconnected-(IC22-NC-Pad29)") (class "Default")
      (node (ref "IC22") (pin "29") (pinfunction "NC_29") (pintype "passive+no_connect"))
    )
    (net (code "73") (name "unconnected-(IC22-NC-Pad30)") (class "Default")
      (node (ref "IC22") (pin "30") (pinfunction "NC_30") (pintype "passive+no_connect"))
    )
    (net (code "74") (name "unconnected-(IC22-NC-Pad32)") (class "Default")
      (node (ref "IC22") (pin "32") (pinfunction "NC_32") (pintype "passive+no_connect"))
    )
    (net (code "75") (name "unconnected-(IC22-NC-Pad33)") (class "Default")
      (node (ref "IC22") (pin "33") (pinfunction "NC_33") (pintype "passive+no_connect"))
    )
    (net (code "76") (name "unconnected-(IC22-NC-Pad34)") (class "Default")
      (node (ref "IC22") (pin "34") (pinfunction "NC_34") (pintype "passive+no_connect"))
    )
    (net (code "77") (name "unconnected-(IC22-NC-Pad40)") (class "Default")
      (node (ref "IC22") (pin "40") (pinfunction "NC_40") (pintype "passive+no_connect"))
    )
    (net (code "78") (name "unconnected-(IC22-NC-Pad41)") (class "Default")
      (node (ref "IC22") (pin "41") (pinfunction "NC_41") (pintype "passive+no_connect"))
    )
    (net (code "79") (name "unconnected-(IC25-NC-Pad2)") (class "Default")
      (node (ref "IC25") (pin "2") (pinfunction "NC_2") (pintype "passive+no_connect"))
    )
    (net (code "80") (name "unconnected-(IC25-NC-Pad3)") (class "Default")
      (node (ref "IC25") (pin "3") (pinfunction "NC_3") (pintype "passive+no_connect"))
    )
    (net (code "81") (name "unconnected-(IC25-NC-Pad4)") (class "Default")
      (node (ref "IC25") (pin "4") (pinfunction "NC_4") (pintype "passive+no_connect"))
    )
    (net (code "82") (name "unconnected-(IC25-NC-Pad13)") (class "Default")
      (node (ref "IC25") (pin "13") (pinfunction "NC_13") (pintype "passive+no_connect"))
    )
    (net (code "83") (name "unconnected-(IC25-NC-Pad14)") (class "Default")
      (node (ref "IC25") (pin "14") (pinfunction "NC_14") (pintype "passive+no_connect"))
    )
    (net (code "84") (name "unconnected-(IC25-NC-Pad17)") (class "Default")
      (node (ref "IC25") (pin "17") (pinfunction "NC_17") (pintype "passive+no_connect"))
    )
    (net (code "85") (name "unconnected-(IC25-SS-Pad15)") (class "Default")
      (node (ref "IC25") (pin "15") (pinfunction "SS_15") (pintype "output+no_connect"))
    )
    (net (code "86") (name "unconnected-(IC28-NC-Pad2)") (class "Default")
      (node (ref "IC28") (pin "2") (pinfunction "NC_2") (pintype "passive"))
    )
    (net (code "87") (name "unconnected-(IC29-NC-Pad4)") (class "Default")
      (node (ref "IC29") (pin "4") (pinfunction "NC_4") (pintype "passive"))
    )
  )
)
